# ig-normal2ver3.net
KiCad netlist of a schematic drawn in EAGLE
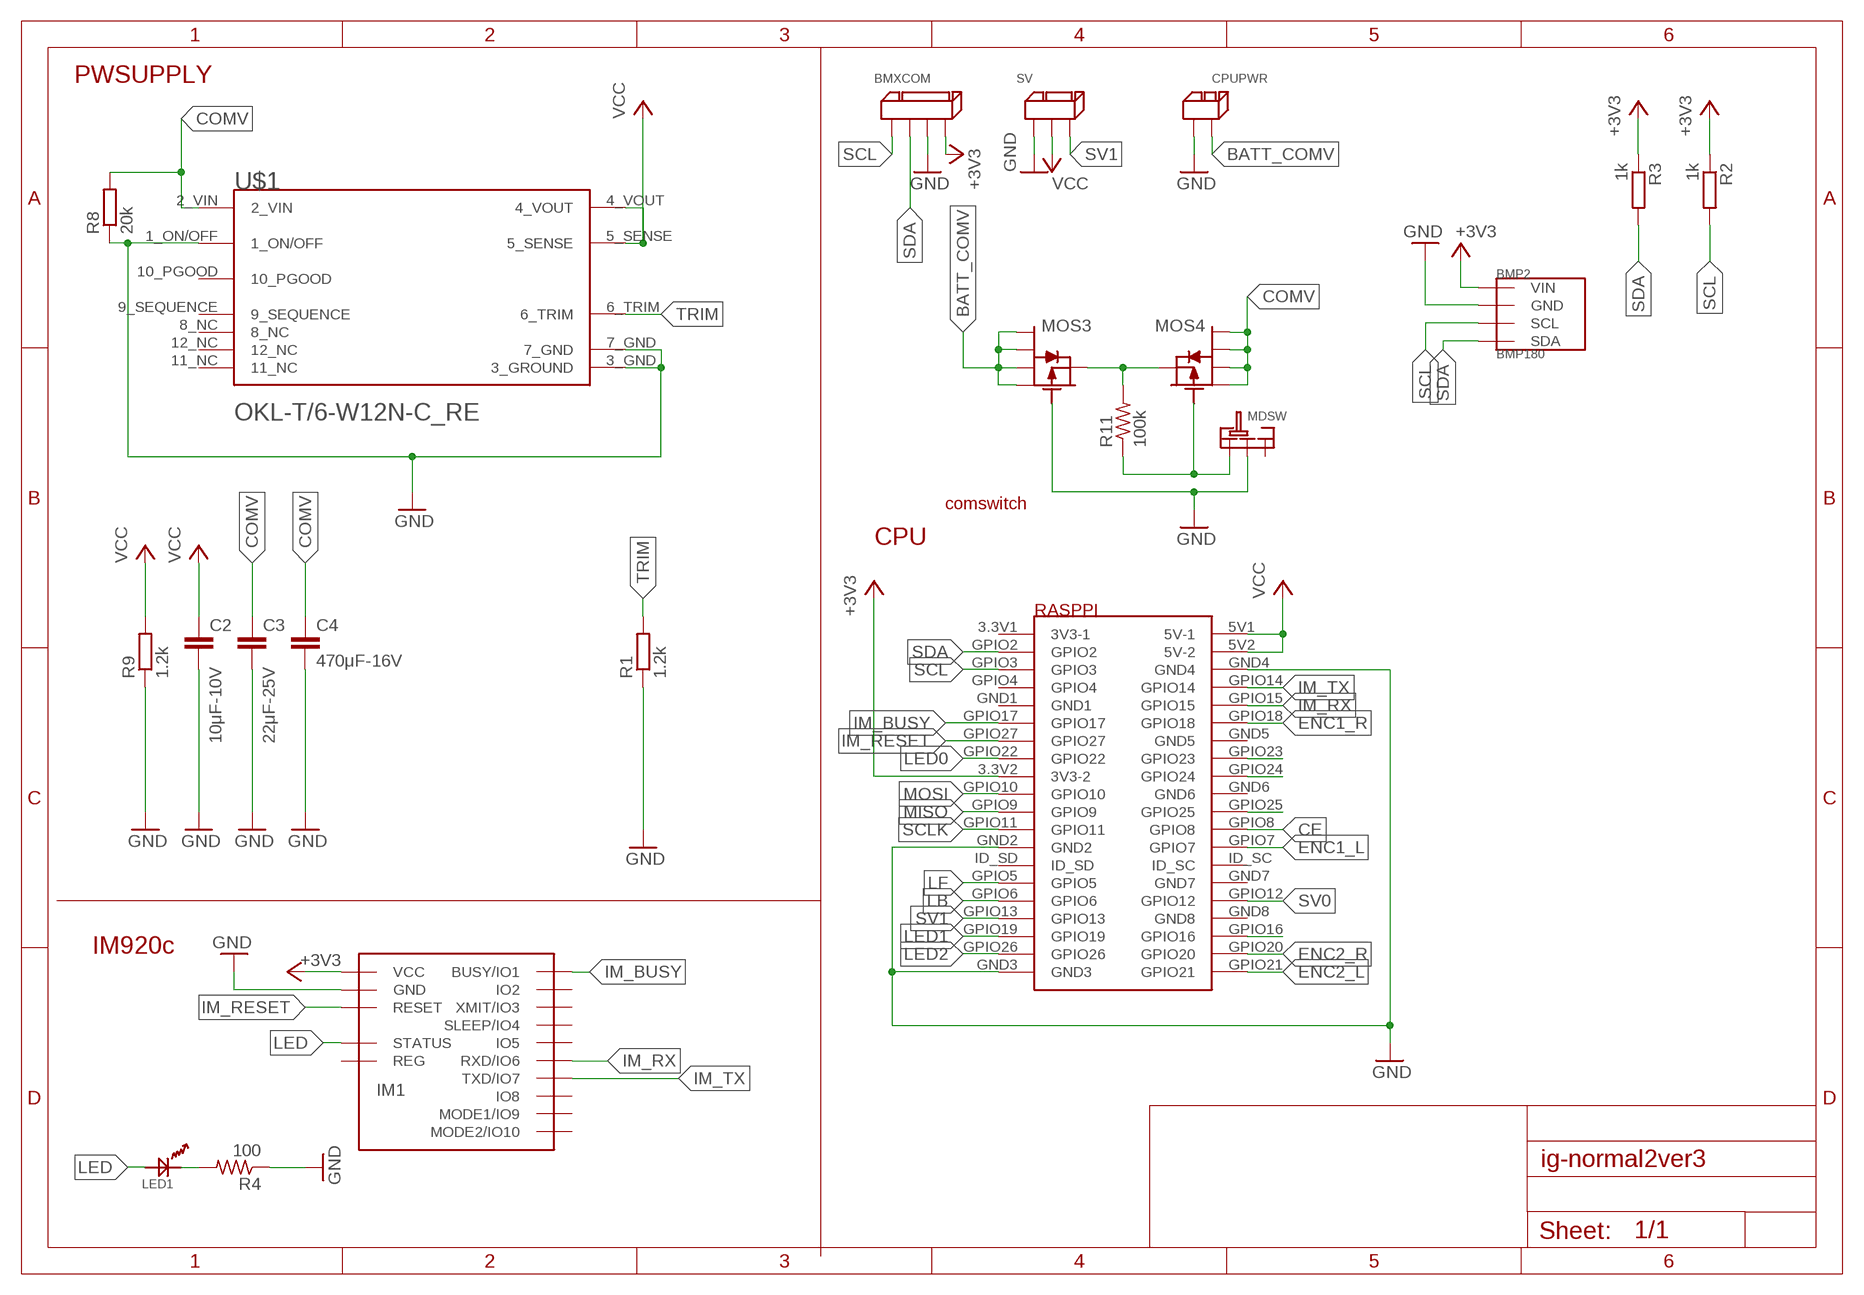
[diagram p0: schematic, sheet 1]

(export (version "E")
  (design (tool "Eeschema 10.0.6"))
  (components
    (comp (ref "BMP2")
      (value "BMP180")
      (footprint "eagle-import:GY-68")
      (libsource (lib "eagle-import") (part "BMP180"))
    )
    (comp (ref "BMXCOM")
      (value "4PIN")
      (footprint "eagle-import:4PIN")
      (libsource (lib "eagle-import") (part "4PIN"))
    )
    (comp (ref "C2")
      (value "10μF-10V")
      (footprint "eagle-import:C0603")
      (libsource (lib "eagle-import") (part "C-EUC0603"))
    )
    (comp (ref "C3")
      (value "22μF-25V")
      (footprint "eagle-import:C0603")
      (libsource (lib "eagle-import") (part "C-EUC0603"))
    )
    (comp (ref "C4")
      (value "470μF-16V")
      (footprint "eagle-import:C0603")
      (libsource (lib "eagle-import") (part "C-EUC0603"))
    )
    (comp (ref "CPUPWR")
      (value "2PIN")
      (footprint "eagle-import:2PIN")
      (libsource (lib "eagle-import") (part "2PIN"))
    )
    (comp (ref "IM1")
      (value "IM920_IM920C")
      (footprint "eagle-import:IM920_IM920C")
      (libsource (lib "eagle-import") (part "IM920_IM920C"))
    )
    (comp (ref "LED1")
      (value "OSXX1608C1A")
      (footprint "eagle-import:OSXX1608C1A")
      (libsource (lib "eagle-import") (part "OSXX1608C1A"))
    )
    (comp (ref "MDSW")
      (value "SRIDE_SWITCH")
      (footprint "eagle-import:SRIDE_SWITCH")
      (libsource (lib "eagle-import") (part "SRIDE_SWITCH"))
    )
    (comp (ref "MOS3")
      (value "PCH_SSM6J808R")
      (footprint "eagle-import:SSM6J808R")
      (libsource (lib "eagle-import") (part "PCH_SSM6J808R"))
    )
    (comp (ref "MOS4")
      (value "PCH_SSM6J808R")
      (footprint "eagle-import:SSM6J808R")
      (libsource (lib "eagle-import") (part "PCH_SSM6J808R"))
    )
    (comp (ref "R1")
      (value "1.2k")
      (footprint "eagle-import:R0805")
      (libsource (lib "eagle-import") (part "R-EU_R0805"))
    )
    (comp (ref "R2")
      (value "1k")
      (footprint "eagle-import:R0603")
      (libsource (lib "eagle-import") (part "R-EU_R0603"))
    )
    (comp (ref "R3")
      (value "1k")
      (footprint "eagle-import:R0603")
      (libsource (lib "eagle-import") (part "R-EU_R0603"))
    )
    (comp (ref "R4")
      (value "100")
      (footprint "eagle-import:R0603")
      (libsource (lib "eagle-import") (part "R-US_R0603"))
    )
    (comp (ref "R8")
      (value "20k")
      (footprint "eagle-import:R0603")
      (libsource (lib "eagle-import") (part "R-EU_R0603"))
    )
    (comp (ref "R9")
      (value "1.2k")
      (footprint "eagle-import:R0805")
      (libsource (lib "eagle-import") (part "R-EU_R0805"))
    )
    (comp (ref "R11")
      (value "100k")
      (footprint "eagle-import:R0603")
      (libsource (lib "eagle-import") (part "R-US_R0603"))
    )
    (comp (ref "RASPPI")
      (value "RASPBERYPIZEROW")
      (footprint "eagle-import:RASPBERYPIZEROW")
      (libsource (lib "eagle-import") (part "RASPBERYPIZEROW"))
    )
    (comp (ref "SV")
      (value "3PIN")
      (footprint "eagle-import:3PIN")
      (libsource (lib "eagle-import") (part "3PIN"))
    )
    (comp (ref "U$1")
      (value "OKL-T/6-W12N-C_RE")
      (footprint "eagle-import:MURATA_IKL-T-6-W12N-C_0_RECOMENDED")
      (libsource (lib "eagle-import") (part "OKL-T/6-W12N-C_RE"))
    )
  )
  (nets
    (net (code "1") (name "+3V3") (class "Default")
      (node (ref "BMP2") (pin "P1") (pinfunction "VIN_P1") (pintype "bidirectional"))
      (node (ref "BMXCOM") (pin "P$4") (pinfunction "P$4_P$4") (pintype "bidirectional"))
      (node (ref "IM1") (pin "$P17") (pinfunction "VCC_$P17") (pintype "bidirectional"))
      (node (ref "R2") (pin "1") (pinfunction "1_1") (pintype "passive"))
      (node (ref "R3") (pin "1") (pinfunction "1_1") (pintype "passive"))
      (node (ref "RASPPI") (pin "3.3V2") (pinfunction "3V3-2_3.3V2") (pintype "bidirectional"))
    )
    (net (code "2") (name "BATT_COMV") (class "Default")
      (node (ref "CPUPWR") (pin "P$2") (pinfunction "P$2_P$2") (pintype "bidirectional"))
      (node (ref "MOS3") (pin "1") (pinfunction "1_1") (pintype "bidirectional"))
      (node (ref "MOS3") (pin "2") (pinfunction "2_2") (pintype "bidirectional"))
      (node (ref "MOS3") (pin "5") (pinfunction "5_5") (pintype "bidirectional"))
      (node (ref "MOS3") (pin "6") (pinfunction "6_6") (pintype "bidirectional"))
    )
    (net (code "3") (name "CE") (class "Default")
      (node (ref "RASPPI") (pin "GPIO8") (pinfunction "GPIO8_GPIO8") (pintype "bidirectional"))
    )
    (net (code "4") (name "COMV") (class "Default")
      (node (ref "C3") (pin "1") (pinfunction "1_1") (pintype "passive"))
      (node (ref "C4") (pin "1") (pinfunction "1_1") (pintype "passive"))
      (node (ref "MOS4") (pin "1") (pinfunction "1_1") (pintype "bidirectional"))
      (node (ref "MOS4") (pin "2") (pinfunction "2_2") (pintype "bidirectional"))
      (node (ref "MOS4") (pin "5") (pinfunction "5_5") (pintype "bidirectional"))
      (node (ref "MOS4") (pin "6") (pinfunction "6_6") (pintype "bidirectional"))
      (node (ref "R8") (pin "2") (pinfunction "2_2") (pintype "passive"))
      (node (ref "U$1") (pin "2_VIN") (pinfunction "2_VIN_2_VIN") (pintype "bidirectional"))
    )
    (net (code "5") (name "ENC1_L") (class "Default")
      (node (ref "RASPPI") (pin "GPIO7") (pinfunction "GPIO7_GPIO7") (pintype "bidirectional"))
    )
    (net (code "6") (name "ENC1_R") (class "Default")
      (node (ref "RASPPI") (pin "GPIO18") (pinfunction "GPIO18_GPIO18") (pintype "bidirectional"))
    )
    (net (code "7") (name "ENC2_L") (class "Default")
      (node (ref "RASPPI") (pin "GPIO21") (pinfunction "GPIO21_GPIO21") (pintype "bidirectional"))
    )
    (net (code "8") (name "ENC2_R") (class "Default")
      (node (ref "RASPPI") (pin "GPIO20") (pinfunction "GPIO20_GPIO20") (pintype "bidirectional"))
    )
    (net (code "9") (name "GND") (class "Default")
      (node (ref "BMP2") (pin "P2") (pinfunction "GND_P2") (pintype "bidirectional"))
      (node (ref "BMXCOM") (pin "P$3") (pinfunction "P$3_P$3") (pintype "bidirectional"))
      (node (ref "C2") (pin "2") (pinfunction "2_2") (pintype "passive"))
      (node (ref "C3") (pin "2") (pinfunction "2_2") (pintype "passive"))
      (node (ref "C4") (pin "2") (pinfunction "2_2") (pintype "passive"))
      (node (ref "CPUPWR") (pin "P$1") (pinfunction "P$1_P$1") (pintype "bidirectional"))
      (node (ref "IM1") (pin "$P18") (pinfunction "GND_$P18") (pintype "bidirectional"))
      (node (ref "MDSW") (pin "LR") (pinfunction "LR_LR") (pintype "bidirectional"))
      (node (ref "MOS3") (pin "3") (pinfunction "3_3") (pintype "bidirectional"))
      (node (ref "R1") (pin "1") (pinfunction "1_1") (pintype "passive"))
      (node (ref "R4") (pin "1") (pinfunction "1_1") (pintype "passive"))
      (node (ref "R8") (pin "1") (pinfunction "1_1") (pintype "passive"))
      (node (ref "R9") (pin "1") (pinfunction "1_1") (pintype "passive"))
      (node (ref "RASPPI") (pin "GND2") (pinfunction "GND2_GND2") (pintype "bidirectional"))
      (node (ref "RASPPI") (pin "GND3") (pinfunction "GND3_GND3") (pintype "bidirectional"))
      (node (ref "RASPPI") (pin "GND4") (pinfunction "GND4_GND4") (pintype "bidirectional"))
      (node (ref "SV") (pin "P$1") (pinfunction "P$1_P$1") (pintype "bidirectional"))
      (node (ref "U$1") (pin "1_ON/OFF") (pinfunction "1_ON/OFF_1_ON/OFF") (pintype "bidirectional"))
      (node (ref "U$1") (pin "3_GND") (pinfunction "3_GROUND_3_GND") (pintype "power_in"))
      (node (ref "U$1") (pin "7_GND") (pinfunction "7_GND_7_GND") (pintype "power_in"))
    )
    (net (code "10") (name "IM_BUSY") (class "Default")
      (node (ref "IM1") (pin "$P1") (pinfunction "BUSY/IO1_$P1") (pintype "bidirectional"))
      (node (ref "RASPPI") (pin "GPIO17") (pinfunction "GPIO17_GPIO17") (pintype "bidirectional"))
    )
    (net (code "11") (name "IM_RESET") (class "Default")
      (node (ref "IM1") (pin "$P19") (pinfunction "RESET_$P19") (pintype "bidirectional"))
      (node (ref "RASPPI") (pin "GPIO27") (pinfunction "GPIO27_GPIO27") (pintype "bidirectional"))
    )
    (net (code "12") (name "IM_RX") (class "Default")
      (node (ref "IM1") (pin "$P6") (pinfunction "RXD/IO6_$P6") (pintype "bidirectional"))
      (node (ref "RASPPI") (pin "GPIO15") (pinfunction "GPIO15_GPIO15") (pintype "bidirectional"))
    )
    (net (code "13") (name "IM_TX") (class "Default")
      (node (ref "IM1") (pin "$P7") (pinfunction "TXD/IO7_$P7") (pintype "bidirectional"))
      (node (ref "RASPPI") (pin "GPIO14") (pinfunction "GPIO14_GPIO14") (pintype "bidirectional"))
    )
    (net (code "14") (name "LB") (class "Default")
      (node (ref "RASPPI") (pin "GPIO6") (pinfunction "GPIO6_GPIO6") (pintype "bidirectional"))
    )
    (net (code "15") (name "LED") (class "Default")
      (node (ref "IM1") (pin "$P15") (pinfunction "STATUS_$P15") (pintype "bidirectional"))
      (node (ref "LED1") (pin "AN") (pinfunction "AN_AN") (pintype "bidirectional"))
    )
    (net (code "16") (name "LED0") (class "Default")
      (node (ref "RASPPI") (pin "GPIO22") (pinfunction "GPIO22_GPIO22") (pintype "bidirectional"))
    )
    (net (code "17") (name "LED1") (class "Default")
      (node (ref "RASPPI") (pin "GPIO19") (pinfunction "GPIO19_GPIO19") (pintype "bidirectional"))
    )
    (net (code "18") (name "LED2") (class "Default")
      (node (ref "RASPPI") (pin "GPIO26") (pinfunction "GPIO26_GPIO26") (pintype "bidirectional"))
    )
    (net (code "19") (name "LF") (class "Default")
      (node (ref "RASPPI") (pin "GPIO5") (pinfunction "GPIO5_GPIO5") (pintype "bidirectional"))
    )
    (net (code "20") (name "MISO") (class "Default")
      (node (ref "RASPPI") (pin "GPIO9") (pinfunction "GPIO9_GPIO9") (pintype "bidirectional"))
    )
    (net (code "21") (name "MOSI") (class "Default")
      (node (ref "RASPPI") (pin "GPIO10") (pinfunction "GPIO10_GPIO10") (pintype "bidirectional"))
    )
    (net (code "22") (name "Net-(LED1-PadCT)") (class "Default")
      (node (ref "LED1") (pin "CT") (pinfunction "CT_CT") (pintype "bidirectional"))
      (node (ref "R4") (pin "2") (pinfunction "2_2") (pintype "passive"))
    )
    (net (code "23") (name "Net-(MDSW-PadL)") (class "Default")
      (node (ref "MDSW") (pin "L") (pinfunction "L_L") (pintype "bidirectional"))
      (node (ref "MOS4") (pin "3") (pinfunction "3_3") (pintype "bidirectional"))
      (node (ref "R11") (pin "1") (pinfunction "1_1") (pintype "passive"))
    )
    (net (code "24") (name "Net-(MOS3-Pad4)") (class "Default")
      (node (ref "MOS3") (pin "4") (pinfunction "4_4") (pintype "bidirectional"))
      (node (ref "MOS4") (pin "4") (pinfunction "4_4") (pintype "bidirectional"))
      (node (ref "R11") (pin "2") (pinfunction "2_2") (pintype "passive"))
    )
    (net (code "25") (name "SCL") (class "Default")
      (node (ref "BMP2") (pin "P3") (pinfunction "SCL_P3") (pintype "bidirectional"))
      (node (ref "BMXCOM") (pin "P$1") (pinfunction "P$1_P$1") (pintype "bidirectional"))
      (node (ref "R2") (pin "2") (pinfunction "2_2") (pintype "passive"))
      (node (ref "RASPPI") (pin "GPIO3") (pinfunction "GPIO3_GPIO3") (pintype "bidirectional"))
    )
    (net (code "26") (name "SCLK") (class "Default")
      (node (ref "RASPPI") (pin "GPIO11") (pinfunction "GPIO11_GPIO11") (pintype "bidirectional"))
    )
    (net (code "27") (name "SDA") (class "Default")
      (node (ref "BMP2") (pin "P4") (pinfunction "SDA_P4") (pintype "bidirectional"))
      (node (ref "BMXCOM") (pin "P$2") (pinfunction "P$2_P$2") (pintype "bidirectional"))
      (node (ref "R3") (pin "2") (pinfunction "2_2") (pintype "passive"))
      (node (ref "RASPPI") (pin "GPIO2") (pinfunction "GPIO2_GPIO2") (pintype "bidirectional"))
    )
    (net (code "28") (name "SV0") (class "Default")
      (node (ref "RASPPI") (pin "GPIO12") (pinfunction "GPIO12_GPIO12") (pintype "bidirectional"))
    )
    (net (code "29") (name "SV1") (class "Default")
      (node (ref "RASPPI") (pin "GPIO13") (pinfunction "GPIO13_GPIO13") (pintype "bidirectional"))
      (node (ref "SV") (pin "P$3") (pinfunction "P$3_P$3") (pintype "bidirectional"))
    )
    (net (code "30") (name "TRIM") (class "Default")
      (node (ref "R1") (pin "2") (pinfunction "2_2") (pintype "passive"))
      (node (ref "U$1") (pin "6_TRIM") (pinfunction "6_TRIM_6_TRIM") (pintype "passive"))
    )
    (net (code "31") (name "VCC") (class "Default")
      (node (ref "C2") (pin "1") (pinfunction "1_1") (pintype "passive"))
      (node (ref "R9") (pin "2") (pinfunction "2_2") (pintype "passive"))
      (node (ref "RASPPI") (pin "5V1") (pinfunction "5V-1_5V1") (pintype "bidirectional"))
      (node (ref "RASPPI") (pin "5V2") (pinfunction "5V-2_5V2") (pintype "bidirectional"))
      (node (ref "SV") (pin "P$2") (pinfunction "P$2_P$2") (pintype "bidirectional"))
      (node (ref "U$1") (pin "4_VOUT") (pinfunction "4_VOUT_4_VOUT") (pintype "bidirectional"))
      (node (ref "U$1") (pin "5_SENSE") (pinfunction "5_SENSE_5_SENSE") (pintype "passive"))
    )
    (net (code "32") (name "unconnected-(IM1-IO2-Pad$P2)") (class "Default")
      (node (ref "IM1") (pin "$P2") (pinfunction "IO2_$P2") (pintype "bidirectional"))
    )
    (net (code "33") (name "unconnected-(IM1-IO5-Pad$P5)") (class "Default")
      (node (ref "IM1") (pin "$P5") (pinfunction "IO5_$P5") (pintype "bidirectional"))
    )
    (net (code "34") (name "unconnected-(IM1-IO8-Pad$P8)") (class "Default")
      (node (ref "IM1") (pin "$P8") (pinfunction "IO8_$P8") (pintype "bidirectional"))
    )
    (net (code "35") (name "unconnected-(IM1-MODE1{slash}IO9-Pad$P9)") (class "Default")
      (node (ref "IM1") (pin "$P9") (pinfunction "MODE1/IO9_$P9") (pintype "bidirectional"))
    )
    (net (code "36") (name "unconnected-(IM1-MODE2{slash}IO10-Pad$P10)") (class "Default")
      (node (ref "IM1") (pin "$P10") (pinfunction "MODE2/IO10_$P10") (pintype "bidirectional"))
    )
    (net (code "37") (name "unconnected-(IM1-REG-Pad$P16)") (class "Default")
      (node (ref "IM1") (pin "$P16") (pinfunction "REG_$P16") (pintype "bidirectional"))
    )
    (net (code "38") (name "unconnected-(IM1-SLEEP{slash}IO4-Pad$P4)") (class "Default")
      (node (ref "IM1") (pin "$P4") (pinfunction "SLEEP/IO4_$P4") (pintype "bidirectional"))
    )
    (net (code "39") (name "unconnected-(IM1-XMIT{slash}IO3-Pad$P3)") (class "Default")
      (node (ref "IM1") (pin "$P3") (pinfunction "XMIT/IO3_$P3") (pintype "bidirectional"))
    )
    (net (code "40") (name "unconnected-(MDSW-PadR)") (class "Default")
      (node (ref "MDSW") (pin "R") (pinfunction "R_R") (pintype "bidirectional"))
    )
    (net (code "41") (name "unconnected-(RASPPI-3V3-1-Pad3.3V1)") (class "Default")
      (node (ref "RASPPI") (pin "3.3V1") (pinfunction "3V3-1_3.3V1") (pintype "bidirectional"))
    )
    (net (code "42") (name "unconnected-(RASPPI-PadGND1)") (class "Default")
      (node (ref "RASPPI") (pin "GND1") (pinfunction "GND1_GND1") (pintype "bidirectional"))
    )
    (net (code "43") (name "unconnected-(RASPPI-PadGND5)") (class "Default")
      (node (ref "RASPPI") (pin "GND5") (pinfunction "GND5_GND5") (pintype "bidirectional"))
    )
    (net (code "44") (name "unconnected-(RASPPI-PadGND6)") (class "Default")
      (node (ref "RASPPI") (pin "GND6") (pinfunction "GND6_GND6") (pintype "bidirectional"))
    )
    (net (code "45") (name "unconnected-(RASPPI-PadGND7)") (class "Default")
      (node (ref "RASPPI") (pin "GND7") (pinfunction "GND7_GND7") (pintype "bidirectional"))
    )
    (net (code "46") (name "unconnected-(RASPPI-PadGND8)") (class "Default")
      (node (ref "RASPPI") (pin "GND8") (pinfunction "GND8_GND8") (pintype "bidirectional"))
    )
    (net (code "47") (name "unconnected-(RASPPI-PadGPIO4)") (class "Default")
      (node (ref "RASPPI") (pin "GPIO4") (pinfunction "GPIO4_GPIO4") (pintype "bidirectional"))
    )
    (net (code "48") (name "unconnected-(RASPPI-PadGPIO16)") (class "Default")
      (node (ref "RASPPI") (pin "GPIO16") (pinfunction "GPIO16_GPIO16") (pintype "bidirectional"))
    )
    (net (code "49") (name "unconnected-(RASPPI-PadGPIO23)") (class "Default")
      (node (ref "RASPPI") (pin "GPIO23") (pinfunction "GPIO23_GPIO23") (pintype "bidirectional"))
    )
    (net (code "50") (name "unconnected-(RASPPI-PadGPIO24)") (class "Default")
      (node (ref "RASPPI") (pin "GPIO24") (pinfunction "GPIO24_GPIO24") (pintype "bidirectional"))
    )
    (net (code "51") (name "unconnected-(RASPPI-PadGPIO25)") (class "Default")
      (node (ref "RASPPI") (pin "GPIO25") (pinfunction "GPIO25_GPIO25") (pintype "bidirectional"))
    )
    (net (code "52") (name "unconnected-(RASPPI-PadID_SC)") (class "Default")
      (node (ref "RASPPI") (pin "ID_SC") (pinfunction "ID_SC_ID_SC") (pintype "bidirectional"))
    )
    (net (code "53") (name "unconnected-(RASPPI-PadID_SD)") (class "Default")
      (node (ref "RASPPI") (pin "ID_SD") (pinfunction "ID_SD_ID_SD") (pintype "bidirectional"))
    )
    (net (code "54") (name "unconnected-(U$1-Pad8_NC)") (class "Default")
      (node (ref "U$1") (pin "8_NC") (pinfunction "8_NC_8_NC") (pintype "passive"))
    )
    (net (code "55") (name "unconnected-(U$1-Pad9_SEQUENCE)") (class "Default")
      (node (ref "U$1") (pin "9_SEQUENCE") (pinfunction "9_SEQUENCE_9_SEQUENCE") (pintype "passive"))
    )
    (net (code "56") (name "unconnected-(U$1-Pad10_PGOOD)") (class "Default")
      (node (ref "U$1") (pin "10_PGOOD") (pinfunction "10_PGOOD_10_PGOOD") (pintype "open_collector"))
    )
    (net (code "57") (name "unconnected-(U$1-Pad11_NC)") (class "Default")
      (node (ref "U$1") (pin "11_NC") (pinfunction "11_NC_11_NC") (pintype "passive"))
    )
    (net (code "58") (name "unconnected-(U$1-Pad12_NC)") (class "Default")
      (node (ref "U$1") (pin "12_NC") (pinfunction "12_NC_12_NC") (pintype "passive"))
    )
  )
)
